# RollerShutterNode_smdnrf.net
KiCad netlist of a schematic drawn in EAGLE
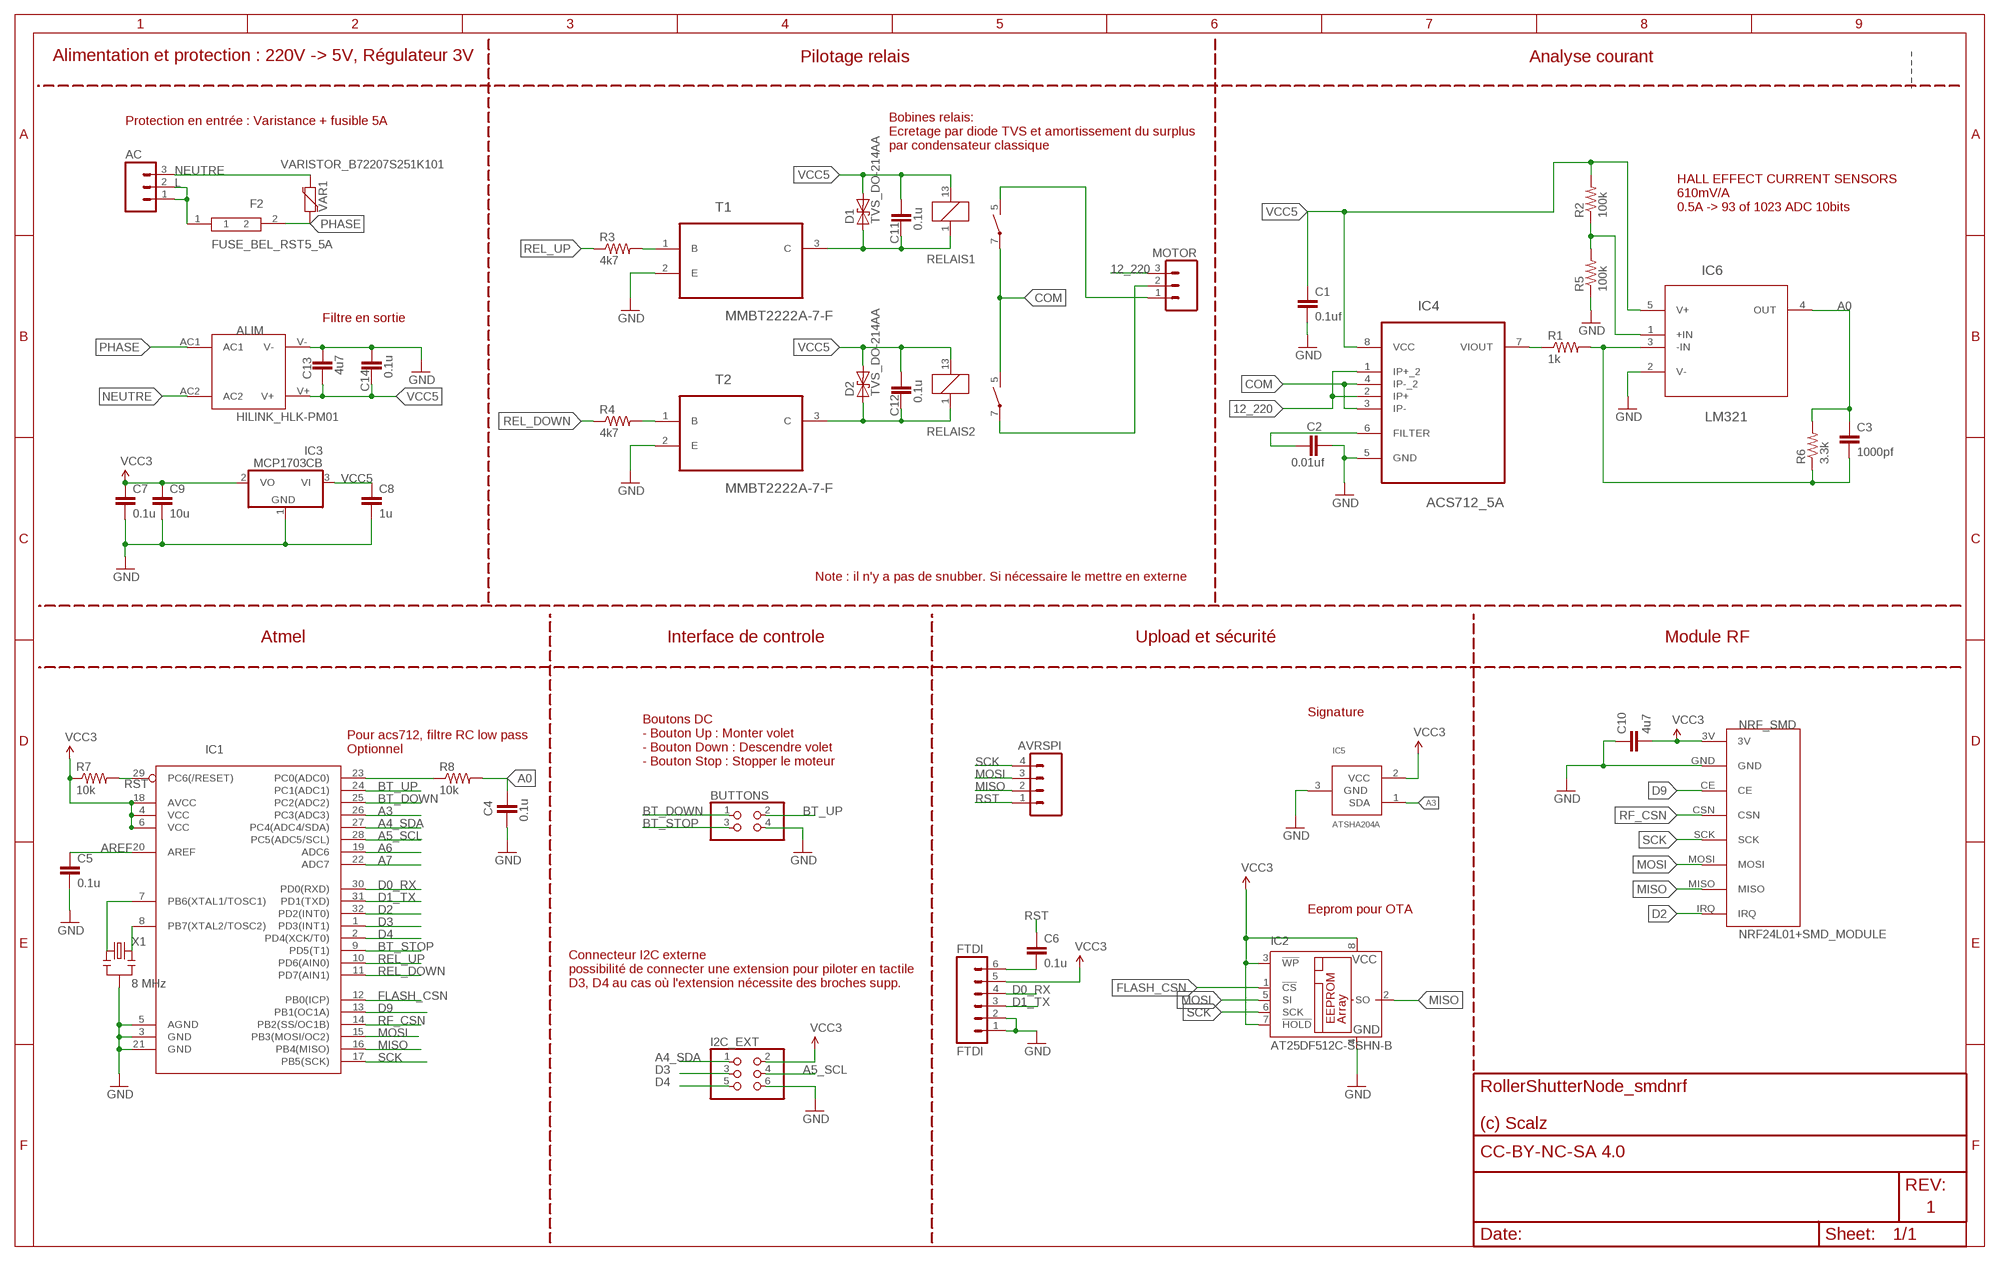
[diagram p0: schematic, sheet 1]

(export (version "E")
  (design (tool "Eeschema 10.0.6"))
  (components
    (comp (ref "AC")
      (value "M03-SCREW-5MM")
      (footprint "eagle-import:SCREWTERMINAL-5MM-3")
      (libsource (lib "eagle-import") (part "M03-SCREW-5MM"))
    )
    (comp (ref "ALIM")
      (value "HILINK_HLK-PM01")
      (footprint "eagle-import:HILINK_HLK-PM01")
      (libsource (lib "eagle-import") (part "HILINK_HLK-PM01"))
    )
    (comp (ref "AVRSPI")
      (value "M04PTH")
      (footprint "eagle-import:1X04")
      (libsource (lib "eagle-import") (part "M04PTH"))
    )
    (comp (ref "BUTTONS")
      (value "PINHD-2X2")
      (footprint "eagle-import:2X02")
      (libsource (lib "eagle-import") (part "PINHD-2X2"))
    )
    (comp (ref "C1")
      (value "0.1uf")
      (footprint "eagle-import:0805-CAP")
      (libsource (lib "eagle-import") (part "CAP0805-CAP"))
    )
    (comp (ref "C2")
      (value "0.01uf")
      (footprint "eagle-import:0805-CAP")
      (libsource (lib "eagle-import") (part "CAP0805-CAP"))
    )
    (comp (ref "C3")
      (value "1000pf")
      (footprint "eagle-import:0805-CAP")
      (libsource (lib "eagle-import") (part "CAP0805-CAP"))
    )
    (comp (ref "C4")
      (value "0.1u")
      (footprint "eagle-import:0805-CAP")
      (libsource (lib "eagle-import") (part "CAP0805-CAP"))
    )
    (comp (ref "C5")
      (value "0.1u")
      (footprint "eagle-import:0805-CAP")
      (libsource (lib "eagle-import") (part "CAP0805-CAP"))
    )
    (comp (ref "C6")
      (value "0.1u")
      (footprint "eagle-import:0805-CAP")
      (libsource (lib "eagle-import") (part "CAP0805-CAP"))
    )
    (comp (ref "C7")
      (value "0.1u")
      (footprint "eagle-import:0805-CAP")
      (libsource (lib "eagle-import") (part "CAP0805-CAP"))
    )
    (comp (ref "C8")
      (value "1u")
      (footprint "eagle-import:0805-CAP")
      (libsource (lib "eagle-import") (part "CAP0805-CAP"))
    )
    (comp (ref "C9")
      (value "10u")
      (footprint "eagle-import:0805-CAP")
      (libsource (lib "eagle-import") (part "CAP0805-CAP"))
    )
    (comp (ref "C10")
      (value "4u7")
      (footprint "eagle-import:0805-CAP")
      (libsource (lib "eagle-import") (part "CAP0805-CAP"))
    )
    (comp (ref "C11")
      (value "0.1u")
      (footprint "eagle-import:0805-CAP")
      (libsource (lib "eagle-import") (part "CAP0805-CAP"))
    )
    (comp (ref "C12")
      (value "0.1u")
      (footprint "eagle-import:0805-CAP")
      (libsource (lib "eagle-import") (part "CAP0805-CAP"))
    )
    (comp (ref "C13")
      (value "4u7")
      (footprint "eagle-import:0805-CAP")
      (libsource (lib "eagle-import") (part "CAP0805-CAP"))
    )
    (comp (ref "C14")
      (value "0.1u")
      (footprint "eagle-import:0805-CAP")
      (libsource (lib "eagle-import") (part "CAP0805-CAP"))
    )
    (comp (ref "D1")
      (value "TVS_DO-214AA")
      (footprint "eagle-import:TVS_DO-214AA")
      (libsource (lib "eagle-import") (part "TVS_DO-214AA"))
    )
    (comp (ref "D2")
      (value "TVS_DO-214AA")
      (footprint "eagle-import:TVS_DO-214AA")
      (libsource (lib "eagle-import") (part "TVS_DO-214AA"))
    )
    (comp (ref "F2")
      (value "FUSE_BEL_RST5_5A")
      (footprint "eagle-import:FUSE_BEL_RST5_5A")
      (libsource (lib "eagle-import") (part "FUSE_BEL_RST5_5A"))
    )
    (comp (ref "FTDI")
      (value "FTDI")
      (footprint "eagle-import:1X06")
      (libsource (lib "eagle-import") (part "M06SIP"))
    )
    (comp (ref "I2C_EXT")
      (value "PINHD-2X3")
      (footprint "eagle-import:2X03")
      (libsource (lib "eagle-import") (part "PINHD-2X3"))
    )
    (comp (ref "IC1")
      (value "ATMega-328")
      (footprint "eagle-import:TQFP32-08")
      (libsource (lib "eagle-import") (part "ATMEGA168/328TQFP32"))
    )
    (comp (ref "IC2")
      (value "AT25DF512C-SSHN-B")
      (footprint "eagle-import:SO-08")
      (fields (field (name "MF") "MICROCHIP") (field (name "MPN") "25AA080/SN"))
      (libsource (lib "eagle-import") (part "25SNAA080"))
    )
    (comp (ref "IC3")
      (value "MCP1703CB")
      (footprint "eagle-import:SOT23")
      (libsource (lib "eagle-import") (part "MCP1703CB"))
    )
    (comp (ref "IC4")
      (value "ACS712_5A")
      (footprint "eagle-import:SOIC127P600X175-8N")
      (fields (field (name "MPN") "ACS712ELCTR-20A-T"))
      (libsource (lib "eagle-import") (part "ACS712ELCTR-20A-T"))
    )
    (comp (ref "IC5")
      (value "ATSHA204A")
      (footprint "eagle-import:SOT23")
      (libsource (lib "eagle-import") (part "ATSHA204A"))
    )
    (comp (ref "IC6")
      (value "LM321")
      (footprint "eagle-import:SOT95P285X120-5N")
      (fields (field (name "MPN") "LM321MF"))
      (libsource (lib "eagle-import") (part "LM321MF"))
    )
    (comp (ref "MOTOR")
      (value "M03-SCREW-5MM")
      (footprint "eagle-import:SCREWTERMINAL-5MM-3")
      (libsource (lib "eagle-import") (part "M03-SCREW-5MM"))
    )
    (comp (ref "NRF_SMD")
      (value "NRF24L01+SMD_MODULE")
      (footprint "eagle-import:NRF24L01+SMD_MODULE")
      (libsource (lib "eagle-import") (part "NRF24L01+SMD_MODULE"))
    )
    (comp (ref "R1")
      (value "1k")
      (footprint "eagle-import:0805-RES")
      (libsource (lib "eagle-import") (part "RESISTOR0805-RES"))
    )
    (comp (ref "R2")
      (value "100k")
      (footprint "eagle-import:0805-RES")
      (libsource (lib "eagle-import") (part "RESISTOR0805-RES"))
    )
    (comp (ref "R3")
      (value "4k7")
      (footprint "eagle-import:0805-RES")
      (libsource (lib "eagle-import") (part "RESISTOR0805-RES"))
    )
    (comp (ref "R4")
      (value "4k7")
      (footprint "eagle-import:0805-RES")
      (libsource (lib "eagle-import") (part "RESISTOR0805-RES"))
    )
    (comp (ref "R5")
      (value "100k")
      (footprint "eagle-import:0805-RES")
      (libsource (lib "eagle-import") (part "RESISTOR0805-RES"))
    )
    (comp (ref "R6")
      (value "3.3k")
      (footprint "eagle-import:0805-RES")
      (libsource (lib "eagle-import") (part "RESISTOR0805-RES"))
    )
    (comp (ref "R7")
      (value "10k")
      (footprint "eagle-import:0805-RES")
      (libsource (lib "eagle-import") (part "RESISTOR0805-RES"))
    )
    (comp (ref "R8")
      (value "10k")
      (footprint "eagle-import:0805-RES")
      (libsource (lib "eagle-import") (part "RESISTOR0805-RES"))
    )
    (comp (ref "RELAIS1")
      (value "Relais G6D")
      (footprint "eagle-import:G6D")
      (libsource (lib "eagle-import") (part "G6D?-1A-ASI12VDC"))
    )
    (comp (ref "RELAIS2")
      (value "Relais G6D")
      (footprint "eagle-import:G6D")
      (libsource (lib "eagle-import") (part "G6D?-1A-ASI12VDC"))
    )
    (comp (ref "T1")
      (value "MMBT2222A-7-F")
      (footprint "eagle-import:SOT103P240X110-3N")
      (libsource (lib "eagle-import") (part "MMBT2222A-7-F"))
    )
    (comp (ref "T2")
      (value "MMBT2222A-7-F")
      (footprint "eagle-import:SOT103P240X110-3N")
      (libsource (lib "eagle-import") (part "MMBT2222A-7-F"))
    )
    (comp (ref "VAR1")
      (value "VARISTOR_B72207S251K101")
      (footprint "eagle-import:VARISTOR_B72207S251K101")
      (libsource (lib "eagle-import") (part "VARISTOR_B72207S251K101"))
    )
    (comp (ref "X1")
      (value "8 MHz")
      (footprint "eagle-import:RESONATOR-SMD")
      (libsource (lib "eagle-import") (part "RESONATORSMD"))
    )
  )
  (nets
    (net (code "1") (name "/A4_SDA") (class "Default")
      (node (ref "I2C_EXT") (pin "1") (pinfunction "1_1") (pintype "passive"))
      (node (ref "IC1") (pin "27") (pinfunction "PC4(ADC4/SDA)_27") (pintype "bidirectional"))
    )
    (net (code "2") (name "/A5_SCL") (class "Default")
      (node (ref "I2C_EXT") (pin "4") (pinfunction "4_4") (pintype "passive"))
      (node (ref "IC1") (pin "28") (pinfunction "PC5(ADC5/SCL)_28") (pintype "bidirectional"))
    )
    (net (code "3") (name "/A6") (class "Default")
      (node (ref "IC1") (pin "19") (pinfunction "ADC6_19") (pintype "bidirectional"))
    )
    (net (code "4") (name "/A7") (class "Default")
      (node (ref "IC1") (pin "22") (pinfunction "ADC7_22") (pintype "bidirectional"))
    )
    (net (code "5") (name "/AREF") (class "Default")
      (node (ref "C5") (pin "1") (pinfunction "1_1") (pintype "passive"))
      (node (ref "IC1") (pin "20") (pinfunction "AREF_20") (pintype "bidirectional"))
    )
    (net (code "6") (name "/BT_DOWN") (class "Default")
      (node (ref "BUTTONS") (pin "1") (pinfunction "1_1") (pintype "passive"))
      (node (ref "IC1") (pin "25") (pinfunction "PC2(ADC2)_25") (pintype "bidirectional"))
    )
    (net (code "7") (name "/BT_STOP") (class "Default")
      (node (ref "BUTTONS") (pin "3") (pinfunction "3_3") (pintype "passive"))
      (node (ref "IC1") (pin "9") (pinfunction "PD5(T1)_9") (pintype "bidirectional"))
    )
    (net (code "8") (name "/BT_UP") (class "Default")
      (node (ref "BUTTONS") (pin "2") (pinfunction "2_2") (pintype "passive"))
      (node (ref "IC1") (pin "24") (pinfunction "PC1(ADC1)_24") (pintype "bidirectional"))
    )
    (net (code "9") (name "/D0_RX") (class "Default")
      (node (ref "FTDI") (pin "4") (pinfunction "4_4") (pintype "passive"))
      (node (ref "IC1") (pin "30") (pinfunction "PD0(RXD)_30") (pintype "bidirectional"))
    )
    (net (code "10") (name "/D1_TX") (class "Default")
      (node (ref "FTDI") (pin "3") (pinfunction "3_3") (pintype "passive"))
      (node (ref "IC1") (pin "31") (pinfunction "PD1(TXD)_31") (pintype "bidirectional"))
    )
    (net (code "11") (name "/D3") (class "Default")
      (node (ref "I2C_EXT") (pin "3") (pinfunction "3_3") (pintype "passive"))
      (node (ref "IC1") (pin "1") (pinfunction "PD3(INT1)_1") (pintype "bidirectional"))
    )
    (net (code "12") (name "/D4") (class "Default")
      (node (ref "I2C_EXT") (pin "5") (pinfunction "5_5") (pintype "passive"))
      (node (ref "IC1") (pin "2") (pinfunction "PD4(XCK/T0)_2") (pintype "bidirectional"))
    )
    (net (code "13") (name "/L") (class "Default")
      (node (ref "AC") (pin "1") (pinfunction "1_1") (pintype "passive"))
      (node (ref "AC") (pin "2") (pinfunction "2_2") (pintype "passive"))
      (node (ref "F2") (pin "1") (pinfunction "1_1") (pintype "bidirectional"))
    )
    (net (code "14") (name "/RST") (class "Default")
      (node (ref "AVRSPI") (pin "1") (pinfunction "1_1") (pintype "passive"))
      (node (ref "C6") (pin "1") (pinfunction "1_1") (pintype "passive"))
      (node (ref "IC1") (pin "29") (pinfunction "PC6(/RESET)_29") (pintype "bidirectional"))
      (node (ref "R7") (pin "2") (pinfunction "2_2") (pintype "passive"))
    )
    (net (code "15") (name "12_220") (class "Default")
      (node (ref "IC4") (pin "1") (pinfunction "IP+_2_1") (pintype "input"))
      (node (ref "IC4") (pin "2") (pinfunction "IP+_2") (pintype "input"))
      (node (ref "MOTOR") (pin "3") (pinfunction "3_3") (pintype "passive"))
    )
    (net (code "16") (name "A0") (class "Default")
      (node (ref "C3") (pin "1") (pinfunction "1_1") (pintype "passive"))
      (node (ref "C4") (pin "2") (pinfunction "2_2") (pintype "passive"))
      (node (ref "IC6") (pin "4") (pinfunction "OUT_4") (pintype "output"))
      (node (ref "R6") (pin "2") (pinfunction "2_2") (pintype "passive"))
      (node (ref "R8") (pin "2") (pinfunction "2_2") (pintype "passive"))
    )
    (net (code "17") (name "A3") (class "Default")
      (node (ref "IC1") (pin "26") (pinfunction "PC3(ADC3)_26") (pintype "bidirectional"))
      (node (ref "IC5") (pin "1") (pinfunction "SDA_1") (pintype "bidirectional"))
    )
    (net (code "18") (name "COM") (class "Default")
      (node (ref "IC4") (pin "3") (pinfunction "IP-_3") (pintype "input"))
      (node (ref "IC4") (pin "4") (pinfunction "IP-_2_4") (pintype "input"))
      (node (ref "RELAIS1") (pin "7") (pinfunction "P_7") (pintype "passive"))
      (node (ref "RELAIS2") (pin "5") (pinfunction "S_5") (pintype "passive"))
    )
    (net (code "19") (name "D2") (class "Default")
      (node (ref "IC1") (pin "32") (pinfunction "PD2(INT0)_32") (pintype "bidirectional"))
      (node (ref "NRF_SMD") (pin "IRQ") (pinfunction "IRQ_IRQ") (pintype "bidirectional"))
    )
    (net (code "20") (name "D9") (class "Default")
      (node (ref "IC1") (pin "13") (pinfunction "PB1(OC1A)_13") (pintype "bidirectional"))
      (node (ref "NRF_SMD") (pin "CE") (pinfunction "CE_CE") (pintype "bidirectional"))
    )
    (net (code "21") (name "FLASH_CSN") (class "Default")
      (node (ref "IC1") (pin "12") (pinfunction "PB0(ICP)_12") (pintype "bidirectional"))
      (node (ref "IC2") (pin "1") (pinfunction "~{CS}_1") (pintype "input"))
    )
    (net (code "22") (name "GND") (class "Default")
      (node (ref "ALIM") (pin "V-") (pinfunction "V-_V-") (pintype "bidirectional"))
      (node (ref "BUTTONS") (pin "4") (pinfunction "4_4") (pintype "passive"))
      (node (ref "C1") (pin "2") (pinfunction "2_2") (pintype "passive"))
      (node (ref "C10") (pin "1") (pinfunction "1_1") (pintype "passive"))
      (node (ref "C13") (pin "2") (pinfunction "2_2") (pintype "passive"))
      (node (ref "C14") (pin "2") (pinfunction "2_2") (pintype "passive"))
      (node (ref "C2") (pin "2") (pinfunction "2_2") (pintype "passive"))
      (node (ref "C4") (pin "1") (pinfunction "1_1") (pintype "passive"))
      (node (ref "C5") (pin "2") (pinfunction "2_2") (pintype "passive"))
      (node (ref "C7") (pin "2") (pinfunction "2_2") (pintype "passive"))
      (node (ref "C8") (pin "2") (pinfunction "2_2") (pintype "passive"))
      (node (ref "C9") (pin "2") (pinfunction "2_2") (pintype "passive"))
      (node (ref "FTDI") (pin "1") (pinfunction "1_1") (pintype "passive"))
      (node (ref "FTDI") (pin "2") (pinfunction "2_2") (pintype "passive"))
      (node (ref "I2C_EXT") (pin "6") (pinfunction "6_6") (pintype "passive"))
      (node (ref "IC1") (pin "21") (pinfunction "GND_21") (pintype "bidirectional"))
      (node (ref "IC1") (pin "3") (pinfunction "GND_3") (pintype "bidirectional"))
      (node (ref "IC1") (pin "5") (pinfunction "AGND_5") (pintype "bidirectional"))
      (node (ref "IC2") (pin "4") (pinfunction "GND_4") (pintype "power_in"))
      (node (ref "IC3") (pin "1") (pinfunction "GND_1") (pintype "passive"))
      (node (ref "IC4") (pin "5") (pinfunction "GND_5") (pintype "passive"))
      (node (ref "IC5") (pin "3") (pinfunction "GND_3") (pintype "bidirectional"))
      (node (ref "IC6") (pin "2") (pinfunction "V-_2") (pintype "power_in"))
      (node (ref "NRF_SMD") (pin "GND") (pinfunction "GND_GND") (pintype "bidirectional"))
      (node (ref "R5") (pin "1") (pinfunction "1_1") (pintype "passive"))
      (node (ref "T1") (pin "2") (pinfunction "E_2") (pintype "passive"))
      (node (ref "T2") (pin "2") (pinfunction "E_2") (pintype "passive"))
      (node (ref "X1") (pin "2") (pinfunction "2_2") (pintype "passive"))
    )
    (net (code "23") (name "MISO") (class "Default")
      (node (ref "AVRSPI") (pin "2") (pinfunction "2_2") (pintype "passive"))
      (node (ref "IC1") (pin "16") (pinfunction "PB4(MISO)_16") (pintype "bidirectional"))
      (node (ref "IC2") (pin "2") (pinfunction "SO_2") (pintype "bidirectional"))
      (node (ref "NRF_SMD") (pin "MISO") (pinfunction "MISO_MISO") (pintype "bidirectional"))
    )
    (net (code "24") (name "MOSI") (class "Default")
      (node (ref "AVRSPI") (pin "3") (pinfunction "3_3") (pintype "passive"))
      (node (ref "IC1") (pin "15") (pinfunction "PB3(MOSI/OC2)_15") (pintype "bidirectional"))
      (node (ref "IC2") (pin "5") (pinfunction "SI_5") (pintype "input"))
      (node (ref "NRF_SMD") (pin "MOSI") (pinfunction "MOSI_MOSI") (pintype "bidirectional"))
    )
    (net (code "25") (name "NEUTRE") (class "Default")
      (node (ref "AC") (pin "3") (pinfunction "3_3") (pintype "passive"))
      (node (ref "ALIM") (pin "AC2") (pinfunction "AC2_AC2") (pintype "bidirectional"))
      (node (ref "VAR1") (pin "1") (pinfunction "1_1") (pintype "passive"))
    )
    (net (code "26") (name "Net-(C6-Pad2)") (class "Default")
      (node (ref "C6") (pin "2") (pinfunction "2_2") (pintype "passive"))
      (node (ref "FTDI") (pin "6") (pinfunction "6_6") (pintype "passive"))
    )
    (net (code "27") (name "Net-(D1-1)") (class "Default")
      (node (ref "C11") (pin "1") (pinfunction "1_1") (pintype "passive"))
      (node (ref "D1") (pin "A") (pinfunction "1_A") (pintype "passive"))
      (node (ref "RELAIS1") (pin "1") (pinfunction "1_1") (pintype "passive"))
      (node (ref "T1") (pin "3") (pinfunction "C_3") (pintype "output"))
    )
    (net (code "28") (name "Net-(D2-1)") (class "Default")
      (node (ref "C12") (pin "1") (pinfunction "1_1") (pintype "passive"))
      (node (ref "D2") (pin "A") (pinfunction "1_A") (pintype "passive"))
      (node (ref "RELAIS2") (pin "1") (pinfunction "1_1") (pintype "passive"))
      (node (ref "T2") (pin "3") (pinfunction "C_3") (pintype "output"))
    )
    (net (code "29") (name "Net-(IC1-PB6(XTAL1{slash}TOSC1))") (class "Default")
      (node (ref "IC1") (pin "7") (pinfunction "PB6(XTAL1/TOSC1)_7") (pintype "bidirectional"))
      (node (ref "X1") (pin "1") (pinfunction "1_1") (pintype "passive"))
    )
    (net (code "30") (name "Net-(IC1-PB7(XTAL2{slash}TOSC2))") (class "Default")
      (node (ref "IC1") (pin "8") (pinfunction "PB7(XTAL2/TOSC2)_8") (pintype "bidirectional"))
      (node (ref "X1") (pin "3") (pinfunction "3_3") (pintype "passive"))
    )
    (net (code "31") (name "Net-(IC1-PC0(ADC0))") (class "Default")
      (node (ref "IC1") (pin "23") (pinfunction "PC0(ADC0)_23") (pintype "bidirectional"))
      (node (ref "R8") (pin "1") (pinfunction "1_1") (pintype "passive"))
    )
    (net (code "32") (name "Net-(IC4-FILTER)") (class "Default")
      (node (ref "C2") (pin "1") (pinfunction "1_1") (pintype "passive"))
      (node (ref "IC4") (pin "6") (pinfunction "FILTER_6") (pintype "input"))
    )
    (net (code "33") (name "Net-(IC4-VIOUT)") (class "Default")
      (node (ref "IC4") (pin "7") (pinfunction "VIOUT_7") (pintype "output"))
      (node (ref "R1") (pin "1") (pinfunction "1_1") (pintype "passive"))
    )
    (net (code "34") (name "Net-(IC6-+IN)") (class "Default")
      (node (ref "IC6") (pin "1") (pinfunction "+IN_1") (pintype "input"))
      (node (ref "R2") (pin "1") (pinfunction "1_1") (pintype "passive"))
      (node (ref "R5") (pin "2") (pinfunction "2_2") (pintype "passive"))
    )
    (net (code "35") (name "Net-(IC6--IN)") (class "Default")
      (node (ref "C3") (pin "2") (pinfunction "2_2") (pintype "passive"))
      (node (ref "IC6") (pin "3") (pinfunction "-IN_3") (pintype "input"))
      (node (ref "R1") (pin "2") (pinfunction "2_2") (pintype "passive"))
      (node (ref "R6") (pin "1") (pinfunction "1_1") (pintype "passive"))
    )
    (net (code "36") (name "Net-(RELAIS1B-S)") (class "Default")
      (node (ref "MOTOR") (pin "1") (pinfunction "1_1") (pintype "passive"))
      (node (ref "RELAIS1") (pin "5") (pinfunction "S_5") (pintype "passive"))
    )
    (net (code "37") (name "Net-(RELAIS2B-P)") (class "Default")
      (node (ref "MOTOR") (pin "2") (pinfunction "2_2") (pintype "passive"))
      (node (ref "RELAIS2") (pin "7") (pinfunction "P_7") (pintype "passive"))
    )
    (net (code "38") (name "Net-(T1-B)") (class "Default")
      (node (ref "R3") (pin "2") (pinfunction "2_2") (pintype "passive"))
      (node (ref "T1") (pin "1") (pinfunction "B_1") (pintype "input"))
    )
    (net (code "39") (name "Net-(T2-B)") (class "Default")
      (node (ref "R4") (pin "2") (pinfunction "2_2") (pintype "passive"))
      (node (ref "T2") (pin "1") (pinfunction "B_1") (pintype "input"))
    )
    (net (code "40") (name "PHASE") (class "Default")
      (node (ref "ALIM") (pin "AC1") (pinfunction "AC1_AC1") (pintype "bidirectional"))
      (node (ref "F2") (pin "2") (pinfunction "2_2") (pintype "bidirectional"))
      (node (ref "VAR1") (pin "2") (pinfunction "2_2") (pintype "passive"))
    )
    (net (code "41") (name "REL_DOWN") (class "Default")
      (node (ref "IC1") (pin "11") (pinfunction "PD7(AIN1)_11") (pintype "bidirectional"))
      (node (ref "R4") (pin "1") (pinfunction "1_1") (pintype "passive"))
    )
    (net (code "42") (name "REL_UP") (class "Default")
      (node (ref "IC1") (pin "10") (pinfunction "PD6(AIN0)_10") (pintype "bidirectional"))
      (node (ref "R3") (pin "1") (pinfunction "1_1") (pintype "passive"))
    )
    (net (code "43") (name "RF_CSN") (class "Default")
      (node (ref "IC1") (pin "14") (pinfunction "PB2(SS/OC1B)_14") (pintype "bidirectional"))
      (node (ref "NRF_SMD") (pin "CSN") (pinfunction "CSN_CSN") (pintype "bidirectional"))
    )
    (net (code "44") (name "SCK") (class "Default")
      (node (ref "AVRSPI") (pin "4") (pinfunction "4_4") (pintype "passive"))
      (node (ref "IC1") (pin "17") (pinfunction "PB5(SCK)_17") (pintype "bidirectional"))
      (node (ref "IC2") (pin "6") (pinfunction "SCK_6") (pintype "input"))
      (node (ref "NRF_SMD") (pin "SCK") (pinfunction "SCK_SCK") (pintype "bidirectional"))
    )
    (net (code "45") (name "VCC3") (class "Default")
      (node (ref "C10") (pin "2") (pinfunction "2_2") (pintype "passive"))
      (node (ref "C7") (pin "1") (pinfunction "1_1") (pintype "passive"))
      (node (ref "C9") (pin "1") (pinfunction "1_1") (pintype "passive"))
      (node (ref "FTDI") (pin "5") (pinfunction "5_5") (pintype "passive"))
      (node (ref "I2C_EXT") (pin "2") (pinfunction "2_2") (pintype "passive"))
      (node (ref "IC1") (pin "18") (pinfunction "AVCC_18") (pintype "bidirectional"))
      (node (ref "IC1") (pin "4") (pinfunction "VCC_4") (pintype "bidirectional"))
      (node (ref "IC1") (pin "6") (pinfunction "VCC_6") (pintype "bidirectional"))
      (node (ref "IC2") (pin "3") (pinfunction "~{WP}_3") (pintype "input"))
      (node (ref "IC2") (pin "7") (pinfunction "~{HOLD}_7") (pintype "input"))
      (node (ref "IC2") (pin "8") (pinfunction "VCC_8") (pintype "power_in"))
      (node (ref "IC3") (pin "2") (pinfunction "VO_2") (pintype "passive"))
      (node (ref "IC5") (pin "2") (pinfunction "VCC_2") (pintype "bidirectional"))
      (node (ref "NRF_SMD") (pin "3V") (pinfunction "3V_3V") (pintype "bidirectional"))
      (node (ref "R7") (pin "1") (pinfunction "1_1") (pintype "passive"))
    )
    (net (code "46") (name "VCC5") (class "Default")
      (node (ref "ALIM") (pin "V+") (pinfunction "V+_V+") (pintype "bidirectional"))
      (node (ref "C1") (pin "1") (pinfunction "1_1") (pintype "passive"))
      (node (ref "C11") (pin "2") (pinfunction "2_2") (pintype "passive"))
      (node (ref "C12") (pin "2") (pinfunction "2_2") (pintype "passive"))
      (node (ref "C13") (pin "1") (pinfunction "1_1") (pintype "passive"))
      (node (ref "C14") (pin "1") (pinfunction "1_1") (pintype "passive"))
      (node (ref "C8") (pin "1") (pinfunction "1_1") (pintype "passive"))
      (node (ref "D1") (pin "C") (pinfunction "2_C") (pintype "passive"))
      (node (ref "D2") (pin "C") (pinfunction "2_C") (pintype "passive"))
      (node (ref "IC3") (pin "3") (pinfunction "VI_3") (pintype "input"))
      (node (ref "IC4") (pin "8") (pinfunction "VCC_8") (pintype "power_in"))
      (node (ref "IC6") (pin "5") (pinfunction "V+_5") (pintype "power_in"))
      (node (ref "R2") (pin "2") (pinfunction "2_2") (pintype "passive"))
      (node (ref "RELAIS1") (pin "13") (pinfunction "2_13") (pintype "passive"))
      (node (ref "RELAIS2") (pin "13") (pinfunction "2_13") (pintype "passive"))
    )
  )
)
